# Telemetry.net
KiCad netlist of a schematic drawn in Altium Designer
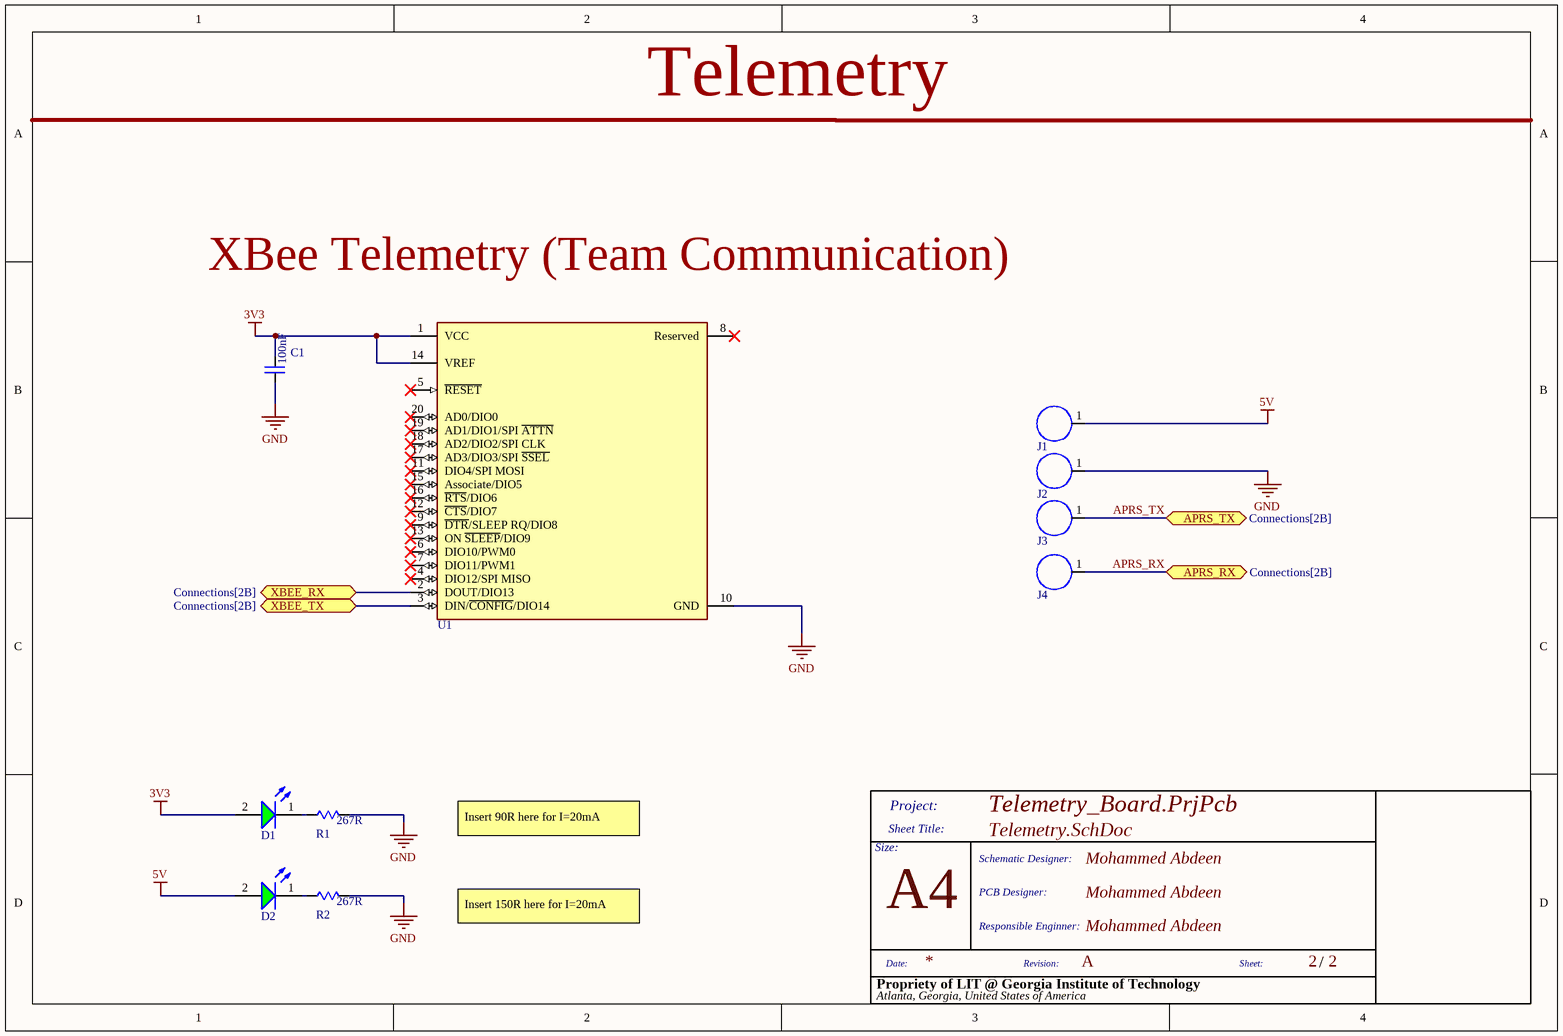
[diagram p0: Telemetry.SchDoc]

(export (version "E")
  (design (tool "Eeschema 10.0.6"))
  (components
    (comp (ref "C1")
      (value "AGC0603X7R500-104KNP")
      (footprint "0603-CAP")
      (description "100nF ±10% 50V Ceramic Capacitor X7R 0603 (1608 Metric)")
      (fields (field (name "MANUFACTURER") "Venkel"))
      (libsource (lib "TelemetrySch") (part "AGC0603X7R500-104KNP"))
    )
    (comp (ref "D1")
      (value "LTST-C190KGKT")
      (footprint "FP-LTST-C190KGKT-MFG")
      (description "Green 571nm LED Indication - Discrete 2V 0603 (1608 Metric)")
      (libsource (lib "MainMCUSch") (part "LED-0603-Green_"))
    )
    (comp (ref "D2")
      (value "LTST-C190KGKT")
      (footprint "FP-LTST-C190KGKT-MFG")
      (description "Green 571nm LED Indication - Discrete 2V 0603 (1608 Metric)")
      (libsource (lib "MainMCUSch") (part "LED-0603-Green_"))
    )
    (comp (ref "J1")
      (value "Solder Pad")
      (footprint "Solder_Pad")
      (description "Use for external and high current connections (cheaper than castellated holes)")
      (libsource (lib "TelemetrySch") (part "Solder_Pad"))
    )
    (comp (ref "J2")
      (value "Solder Pad")
      (footprint "Solder_Pad")
      (description "Use for external and high current connections (cheaper than castellated holes)")
      (libsource (lib "TelemetrySch") (part "Solder_Pad"))
    )
    (comp (ref "J3")
      (value "Solder Pad")
      (footprint "Solder_Pad")
      (description "Use for external and high current connections (cheaper than castellated holes)")
      (libsource (lib "TelemetrySch") (part "Solder_Pad"))
    )
    (comp (ref "J4")
      (value "Solder Pad")
      (footprint "Solder_Pad")
      (description "Use for external and high current connections (cheaper than castellated holes)")
      (libsource (lib "TelemetrySch") (part "Solder_Pad"))
    )
    (comp (ref "R1")
      (value "ERJ-3EKF2670V")
      (footprint "0603-RES")
      (description "267 Ohms ±1% 0.1W, 1/10W Chip Resistor 0603 (1608 Metric) Automotive AEC-Q200 Thick Film")
      (fields (field (name "MANUFACTURER") "Panasonic Electronic Components"))
      (libsource (lib "MainMCUSch") (part "RES-0603-267R"))
    )
    (comp (ref "R2")
      (value "ERJ-3EKF2670V")
      (footprint "0603-RES")
      (description "267 Ohms ±1% 0.1W, 1/10W Chip Resistor 0603 (1608 Metric) Automotive AEC-Q200 Thick Film")
      (fields (field (name "MANUFACTURER") "Panasonic Electronic Components"))
      (libsource (lib "MainMCUSch") (part "RES-0603-267R"))
    )
    (comp (ref "U1")
      (value "XBP9B-XCST-001")
      (footprint "XBee")
      (description "General ISM < 1GHz Transceiver Module 900MHz Antenna Not Included, RP-SMA Through Hole")
      (libsource (lib "TelemetrySch") (part "XBee"))
    )
  )
  (nets
    (net (code "1") (name "/APRS_RX") (class "Default") (node (ref "J4") (pin "1") (pintype "passive")))
    (net (code "2") (name "/APRS_TX") (class "Default") (node (ref "J3") (pin "1") (pintype "passive")))
    (net (code "3") (name "/XBEE_RX") (class "Default")
      (node (ref "U1") (pin "2") (pinfunction "DOUT/DIO13_2") (pintype "bidirectional"))
    )
    (net (code "4") (name "/XBEE_TX") (class "Default")
      (node (ref "U1") (pin "3") (pinfunction "DIN/~{CONFIG}/DIO14_3") (pintype "bidirectional"))
    )
    (net (code "5") (name "3V3") (class "Default")
      (node (ref "C1") (pin "2") (pintype "passive"))
      (node (ref "D1") (pin "2") (pinfunction "A_2") (pintype "passive"))
      (node (ref "U1") (pin "1") (pinfunction "VCC_1") (pintype "power_in"))
      (node (ref "U1") (pin "14") (pinfunction "VREF_14") (pintype "passive"))
    )
    (net (code "6") (name "5V") (class "Default")
      (node (ref "D2") (pin "2") (pinfunction "A_2") (pintype "passive"))
      (node (ref "J1") (pin "1") (pintype "passive"))
    )
    (net (code "7") (name "GND") (class "Default")
      (node (ref "C1") (pin "1") (pintype "passive"))
      (node (ref "J2") (pin "1") (pintype "passive"))
      (node (ref "R1") (pin "2") (pintype "passive"))
      (node (ref "R2") (pin "2") (pintype "passive"))
      (node (ref "U1") (pin "10") (pinfunction "GND_10") (pintype "power_in"))
    )
    (net (code "8") (name "Net-(D1-K)") (class "Default")
      (node (ref "D1") (pin "1") (pinfunction "K_1") (pintype "passive"))
      (node (ref "R1") (pin "1") (pintype "passive"))
    )
    (net (code "9") (name "Net-(D2-K)") (class "Default")
      (node (ref "D2") (pin "1") (pinfunction "K_1") (pintype "passive"))
      (node (ref "R2") (pin "1") (pintype "passive"))
    )
    (net (code "10") (name "unconnected-(U1-AD0{slash}DIO0-Pad20)") (class "Default")
      (node (ref "U1") (pin "20") (pinfunction "AD0/DIO0_20") (pintype "bidirectional+no_connect"))
    )
    (net (code "11") (name "unconnected-(U1-AD1{slash}DIO1{slash}SPI_~{ATTN}-Pad19)") (class "Default")
      (node (ref "U1") (pin "19") (pinfunction "AD1/DIO1/SPI_~{ATTN}_19") (pintype "bidirectional+no_connect"))
    )
    (net (code "12") (name "unconnected-(U1-AD2{slash}DIO2{slash}SPI_CLK-Pad18)") (class "Default")
      (node (ref "U1") (pin "18") (pinfunction "AD2/DIO2/SPI_CLK_18") (pintype "bidirectional+no_connect"))
    )
    (net (code "13") (name "unconnected-(U1-AD3{slash}DIO3{slash}SPI_~{SSEL}-Pad17)") (class "Default")
      (node (ref "U1") (pin "17") (pinfunction "AD3/DIO3/SPI_~{SSEL}_17") (pintype "bidirectional+no_connect"))
    )
    (net (code "14") (name "unconnected-(U1-Associate{slash}DIO5-Pad15)") (class "Default")
      (node (ref "U1") (pin "15") (pinfunction "Associate/DIO5_15") (pintype "bidirectional+no_connect"))
    )
    (net (code "15") (name "unconnected-(U1-DIO4{slash}SPI_MOSI-Pad11)") (class "Default")
      (node (ref "U1") (pin "11") (pinfunction "DIO4/SPI_MOSI_11") (pintype "bidirectional+no_connect"))
    )
    (net (code "16") (name "unconnected-(U1-DIO10{slash}PWM0-Pad6)") (class "Default")
      (node (ref "U1") (pin "6") (pinfunction "DIO10/PWM0_6") (pintype "bidirectional+no_connect"))
    )
    (net (code "17") (name "unconnected-(U1-DIO11{slash}PWM1-Pad7)") (class "Default")
      (node (ref "U1") (pin "7") (pinfunction "DIO11/PWM1_7") (pintype "bidirectional+no_connect"))
    )
    (net (code "18") (name "unconnected-(U1-DIO12{slash}SPI_MISO-Pad4)") (class "Default")
      (node (ref "U1") (pin "4") (pinfunction "DIO12/SPI_MISO_4") (pintype "bidirectional+no_connect"))
    )
    (net (code "19") (name "unconnected-(U1-ON_~{SLEEP}{slash}DIO9-Pad13)") (class "Default")
      (node (ref "U1") (pin "13") (pinfunction "ON_~{SLEEP}/DIO9_13") (pintype "bidirectional+no_connect"))
    )
    (net (code "20") (name "unconnected-(U1-Reserved-Pad8)") (class "Default")
      (node (ref "U1") (pin "8") (pinfunction "Reserved_8") (pintype "passive+no_connect"))
    )
    (net (code "21") (name "unconnected-(U1-~{CTS}{slash}DIO7-Pad12)") (class "Default")
      (node (ref "U1") (pin "12") (pinfunction "~{CTS}/DIO7_12") (pintype "bidirectional+no_connect"))
    )
    (net (code "22") (name "unconnected-(U1-~{DTR}{slash}SLEEP_RQ{slash}DIO8-Pad9)") (class "Default")
      (node (ref "U1") (pin "9") (pinfunction "~{DTR}/SLEEP_RQ/DIO8_9") (pintype "bidirectional+no_connect"))
    )
    (net (code "23") (name "unconnected-(U1-~{RESET}-Pad5)") (class "Default")
      (node (ref "U1") (pin "5") (pinfunction "~{RESET}_5") (pintype "input+no_connect"))
    )
    (net (code "24") (name "unconnected-(U1-~{RTS}{slash}DIO6-Pad16)") (class "Default")
      (node (ref "U1") (pin "16") (pinfunction "~{RTS}/DIO6_16") (pintype "bidirectional+no_connect"))
    )
  )
)
